# toshiba_board.net
KiCad netlist of a schematic drawn in EAGLE
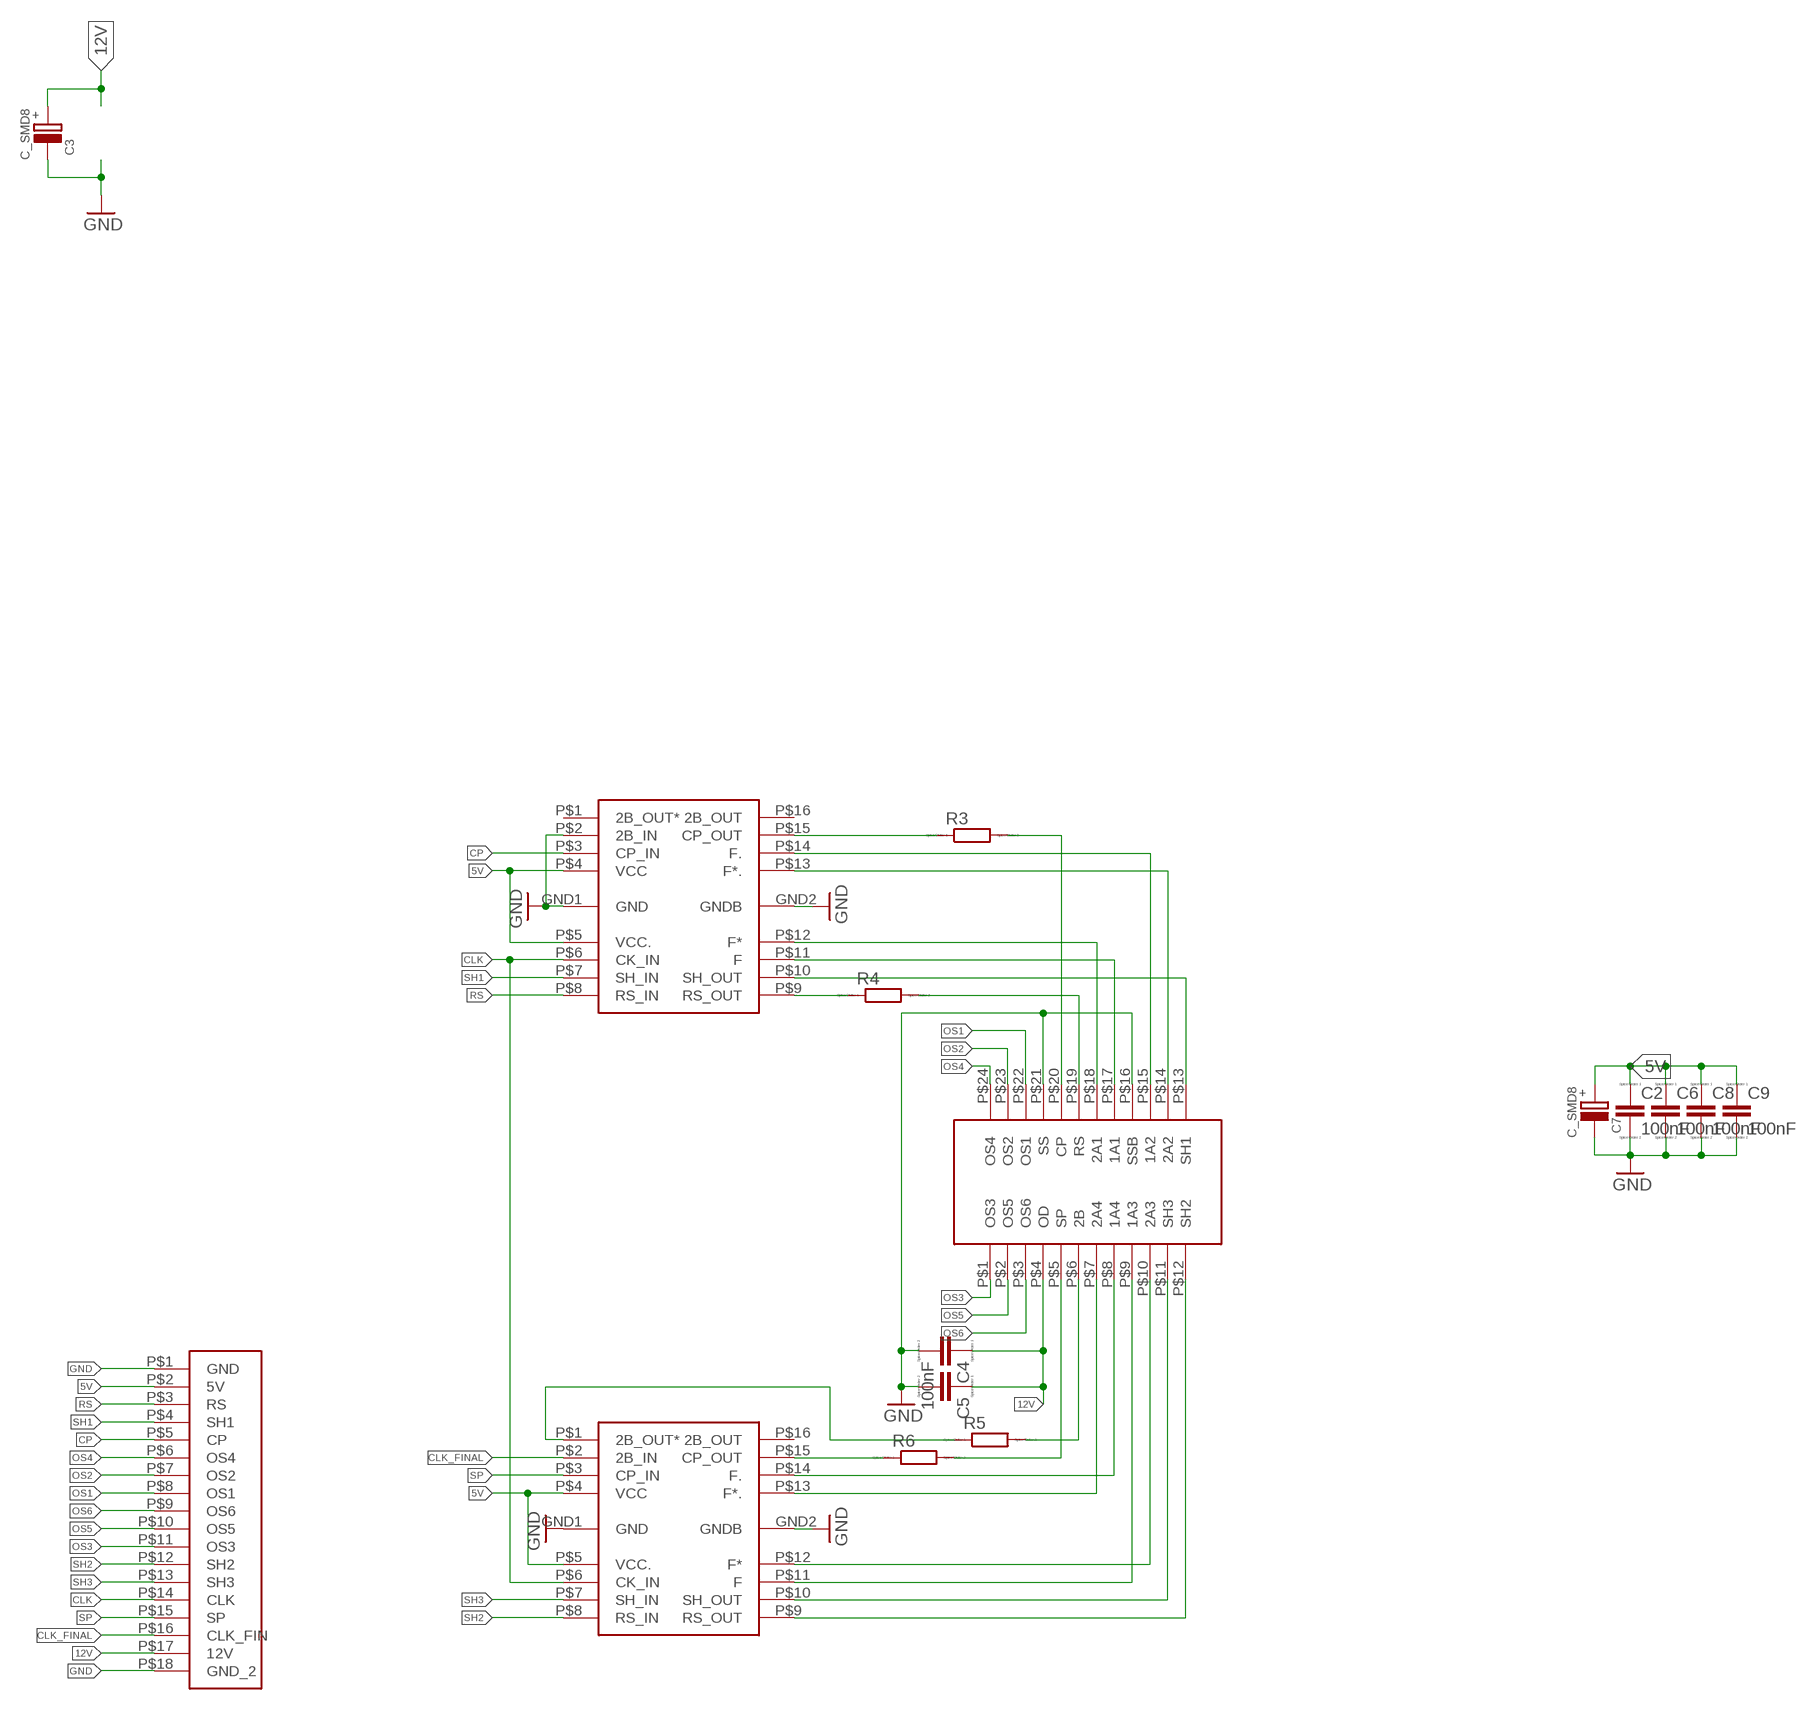
[diagram p0: schematic, sheet 1]

(export (version "E")
  (design (tool "Eeschema 10.0.6"))
  (components
    (comp (ref "C2")
      (value "100nF")
      (footprint "eagle-import:C0603")
      (libsource (lib "eagle-import") (part "C-EUC0603"))
    )
    (comp (ref "C3")
      (value "C_SMD8")
      (footprint "eagle-import:C-SMD-8MM")
      (libsource (lib "eagle-import") (part "C_SMD8"))
    )
    (comp (ref "C4")
      (value "100nF")
      (footprint "eagle-import:C0603")
      (libsource (lib "eagle-import") (part "C-EUC0603"))
    )
    (comp (ref "C5")
      (value "C-EUC0805")
      (footprint "eagle-import:C0805")
      (libsource (lib "eagle-import") (part "C-EUC0805"))
    )
    (comp (ref "C6")
      (value "100nF")
      (footprint "eagle-import:C0603")
      (libsource (lib "eagle-import") (part "C-EUC0603"))
    )
    (comp (ref "C7")
      (value "C_SMD8")
      (footprint "eagle-import:C-SMD-8MM")
      (libsource (lib "eagle-import") (part "C_SMD8"))
    )
    (comp (ref "C8")
      (value "100nF")
      (footprint "eagle-import:C0603")
      (libsource (lib "eagle-import") (part "C-EUC0603"))
    )
    (comp (ref "C9")
      (value "100nF")
      (footprint "eagle-import:C0603")
      (libsource (lib "eagle-import") (part "C-EUC0603"))
    )
    (comp (ref "R3")
      (value "R-EU_R0603")
      (footprint "eagle-import:R0603")
      (libsource (lib "eagle-import") (part "R-EU_R0603"))
    )
    (comp (ref "R4")
      (value "R-EU_R0603")
      (footprint "eagle-import:R0603")
      (libsource (lib "eagle-import") (part "R-EU_R0603"))
    )
    (comp (ref "R5")
      (value "R-EU_R0603")
      (footprint "eagle-import:R0603")
      (libsource (lib "eagle-import") (part "R-EU_R0603"))
    )
    (comp (ref "R6")
      (value "R-EU_R0603")
      (footprint "eagle-import:R0603")
      (libsource (lib "eagle-import") (part "R-EU_R0603"))
    )
    (comp (ref "U$1")
      (value "TB62801F")
      (footprint "eagle-import:TB62801F")
      (libsource (lib "eagle-import") (part "TB62801F"))
    )
    (comp (ref "U$2")
      (value "TCD2700TCD")
      (footprint "eagle-import:TCD2700")
      (libsource (lib "eagle-import") (part "TCD2700TCD"))
    )
    (comp (ref "U$3")
      (value "TB62801F")
      (footprint "eagle-import:TB62801F")
      (libsource (lib "eagle-import") (part "TB62801F"))
    )
    (comp (ref "U$4")
      (value "PIN_18")
      (footprint "eagle-import:PAD_18")
      (libsource (lib "eagle-import") (part "PIN_18"))
    )
  )
  (nets
    (net (code "1") (name "5V") (class "Default")
      (node (ref "C2") (pin "1") (pinfunction "1_1") (pintype "passive"))
      (node (ref "C6") (pin "1") (pinfunction "1_1") (pintype "passive"))
      (node (ref "C7") (pin "+") (pinfunction "+_+") (pintype "bidirectional"))
      (node (ref "C8") (pin "1") (pinfunction "1_1") (pintype "passive"))
      (node (ref "C9") (pin "1") (pinfunction "1_1") (pintype "passive"))
      (node (ref "U$1") (pin "P$4") (pinfunction "VCC_P$4") (pintype "bidirectional"))
      (node (ref "U$1") (pin "P$5") (pinfunction "VCC._P$5") (pintype "bidirectional"))
      (node (ref "U$3") (pin "P$4") (pinfunction "VCC_P$4") (pintype "bidirectional"))
      (node (ref "U$3") (pin "P$5") (pinfunction "VCC._P$5") (pintype "bidirectional"))
      (node (ref "U$4") (pin "P$2") (pinfunction "5V_P$2") (pintype "bidirectional"))
    )
    (net (code "2") (name "12V") (class "Default")
      (node (ref "C3") (pin "+") (pinfunction "+_+") (pintype "bidirectional"))
      (node (ref "C4") (pin "1") (pinfunction "1_1") (pintype "passive"))
      (node (ref "C5") (pin "1") (pinfunction "1_1") (pintype "passive"))
      (node (ref "U$2") (pin "P$4") (pinfunction "OD_P$4") (pintype "bidirectional"))
      (node (ref "U$4") (pin "P$17") (pinfunction "12V_P$17") (pintype "bidirectional"))
    )
    (net (code "3") (name "CLK") (class "Default")
      (node (ref "U$1") (pin "P$6") (pinfunction "CK_IN_P$6") (pintype "bidirectional"))
      (node (ref "U$3") (pin "P$6") (pinfunction "CK_IN_P$6") (pintype "bidirectional"))
      (node (ref "U$4") (pin "P$14") (pinfunction "CLK_P$14") (pintype "bidirectional"))
    )
    (net (code "4") (name "CLK_FINAL") (class "Default")
      (node (ref "U$1") (pin "P$2") (pinfunction "2B_IN_P$2") (pintype "bidirectional"))
      (node (ref "U$4") (pin "P$16") (pinfunction "CLK_FIN_P$16") (pintype "bidirectional"))
    )
    (net (code "5") (name "CP") (class "Default")
      (node (ref "U$3") (pin "P$3") (pinfunction "CP_IN_P$3") (pintype "bidirectional"))
      (node (ref "U$4") (pin "P$5") (pinfunction "CP_P$5") (pintype "bidirectional"))
    )
    (net (code "6") (name "GND") (class "Default")
      (node (ref "C2") (pin "2") (pinfunction "2_2") (pintype "passive"))
      (node (ref "C3") (pin "-") (pinfunction "-_-") (pintype "bidirectional"))
      (node (ref "C4") (pin "2") (pinfunction "2_2") (pintype "passive"))
      (node (ref "C5") (pin "2") (pinfunction "2_2") (pintype "passive"))
      (node (ref "C6") (pin "2") (pinfunction "2_2") (pintype "passive"))
      (node (ref "C7") (pin "-") (pinfunction "-_-") (pintype "bidirectional"))
      (node (ref "C8") (pin "2") (pinfunction "2_2") (pintype "passive"))
      (node (ref "C9") (pin "2") (pinfunction "2_2") (pintype "passive"))
      (node (ref "U$1") (pin "GND1") (pinfunction "GND_GND1") (pintype "bidirectional"))
      (node (ref "U$1") (pin "GND2") (pinfunction "GNDB_GND2") (pintype "bidirectional"))
      (node (ref "U$2") (pin "P$16") (pinfunction "SSB_P$16") (pintype "bidirectional"))
      (node (ref "U$2") (pin "P$21") (pinfunction "SS_P$21") (pintype "bidirectional"))
      (node (ref "U$3") (pin "GND1") (pinfunction "GND_GND1") (pintype "bidirectional"))
      (node (ref "U$3") (pin "GND2") (pinfunction "GNDB_GND2") (pintype "bidirectional"))
      (node (ref "U$3") (pin "P$2") (pinfunction "2B_IN_P$2") (pintype "bidirectional"))
      (node (ref "U$4") (pin "P$1") (pinfunction "GND_P$1") (pintype "bidirectional"))
      (node (ref "U$4") (pin "P$18") (pinfunction "GND_2_P$18") (pintype "bidirectional"))
    )
    (net (code "7") (name "Net-(U$1-2B_OUT*)") (class "Default")
      (node (ref "R5") (pin "1") (pinfunction "1_1") (pintype "passive"))
      (node (ref "U$1") (pin "P$1") (pinfunction "2B_OUT*_P$1") (pintype "bidirectional"))
    )
    (net (code "8") (name "Net-(U$1-CP_OUT)") (class "Default")
      (node (ref "R6") (pin "1") (pinfunction "1_1") (pintype "passive"))
      (node (ref "U$1") (pin "P$15") (pinfunction "CP_OUT_P$15") (pintype "bidirectional"))
    )
    (net (code "9") (name "Net-(U$1-F)") (class "Default")
      (node (ref "U$1") (pin "P$11") (pinfunction "F_P$11") (pintype "bidirectional"))
      (node (ref "U$2") (pin "P$9") (pinfunction "1A3_P$9") (pintype "bidirectional"))
    )
    (net (code "10") (name "Net-(U$1-F*)") (class "Default")
      (node (ref "U$1") (pin "P$12") (pinfunction "F*_P$12") (pintype "bidirectional"))
      (node (ref "U$2") (pin "P$10") (pinfunction "2A3_P$10") (pintype "bidirectional"))
    )
    (net (code "11") (name "Net-(U$1-F*.)") (class "Default")
      (node (ref "U$1") (pin "P$13") (pinfunction "F*._P$13") (pintype "bidirectional"))
      (node (ref "U$2") (pin "P$7") (pinfunction "2A4_P$7") (pintype "bidirectional"))
    )
    (net (code "12") (name "Net-(U$1-F.)") (class "Default")
      (node (ref "U$1") (pin "P$14") (pinfunction "F._P$14") (pintype "bidirectional"))
      (node (ref "U$2") (pin "P$8") (pinfunction "1A4_P$8") (pintype "bidirectional"))
    )
    (net (code "13") (name "Net-(U$1-RS_OUT)") (class "Default")
      (node (ref "U$1") (pin "P$9") (pinfunction "RS_OUT_P$9") (pintype "bidirectional"))
      (node (ref "U$2") (pin "P$12") (pinfunction "SH2_P$12") (pintype "bidirectional"))
    )
    (net (code "14") (name "Net-(U$1-SH_OUT)") (class "Default")
      (node (ref "U$1") (pin "P$10") (pinfunction "SH_OUT_P$10") (pintype "bidirectional"))
      (node (ref "U$2") (pin "P$11") (pinfunction "SH3_P$11") (pintype "bidirectional"))
    )
    (net (code "15") (name "Net-(U$2-1A1)") (class "Default")
      (node (ref "U$2") (pin "P$17") (pinfunction "1A1_P$17") (pintype "bidirectional"))
      (node (ref "U$3") (pin "P$11") (pinfunction "F_P$11") (pintype "bidirectional"))
    )
    (net (code "16") (name "Net-(U$2-1A2)") (class "Default")
      (node (ref "U$2") (pin "P$15") (pinfunction "1A2_P$15") (pintype "bidirectional"))
      (node (ref "U$3") (pin "P$14") (pinfunction "F._P$14") (pintype "bidirectional"))
    )
    (net (code "17") (name "Net-(U$2-2A1)") (class "Default")
      (node (ref "U$2") (pin "P$18") (pinfunction "2A1_P$18") (pintype "bidirectional"))
      (node (ref "U$3") (pin "P$12") (pinfunction "F*_P$12") (pintype "bidirectional"))
    )
    (net (code "18") (name "Net-(U$2-2A2)") (class "Default")
      (node (ref "U$2") (pin "P$14") (pinfunction "2A2_P$14") (pintype "bidirectional"))
      (node (ref "U$3") (pin "P$13") (pinfunction "F*._P$13") (pintype "bidirectional"))
    )
    (net (code "19") (name "Net-(U$2-2B)") (class "Default")
      (node (ref "R5") (pin "2") (pinfunction "2_2") (pintype "passive"))
      (node (ref "U$2") (pin "P$6") (pinfunction "2B_P$6") (pintype "bidirectional"))
    )
    (net (code "20") (name "Net-(U$2-CP)") (class "Default")
      (node (ref "R3") (pin "2") (pinfunction "2_2") (pintype "passive"))
      (node (ref "U$2") (pin "P$20") (pinfunction "CP_P$20") (pintype "bidirectional"))
    )
    (net (code "21") (name "Net-(U$2-RS)") (class "Default")
      (node (ref "R4") (pin "2") (pinfunction "2_2") (pintype "passive"))
      (node (ref "U$2") (pin "P$19") (pinfunction "RS_P$19") (pintype "bidirectional"))
    )
    (net (code "22") (name "Net-(U$2-SH1)") (class "Default")
      (node (ref "U$2") (pin "P$13") (pinfunction "SH1_P$13") (pintype "bidirectional"))
      (node (ref "U$3") (pin "P$10") (pinfunction "SH_OUT_P$10") (pintype "bidirectional"))
    )
    (net (code "23") (name "Net-(U$2-SP)") (class "Default")
      (node (ref "R6") (pin "2") (pinfunction "2_2") (pintype "passive"))
      (node (ref "U$2") (pin "P$5") (pinfunction "SP_P$5") (pintype "bidirectional"))
    )
    (net (code "24") (name "Net-(U$3-CP_OUT)") (class "Default")
      (node (ref "R3") (pin "1") (pinfunction "1_1") (pintype "passive"))
      (node (ref "U$3") (pin "P$15") (pinfunction "CP_OUT_P$15") (pintype "bidirectional"))
    )
    (net (code "25") (name "Net-(U$3-RS_OUT)") (class "Default")
      (node (ref "R4") (pin "1") (pinfunction "1_1") (pintype "passive"))
      (node (ref "U$3") (pin "P$9") (pinfunction "RS_OUT_P$9") (pintype "bidirectional"))
    )
    (net (code "26") (name "OS1") (class "Default")
      (node (ref "U$2") (pin "P$22") (pinfunction "OS1_P$22") (pintype "bidirectional"))
      (node (ref "U$4") (pin "P$8") (pinfunction "OS1_P$8") (pintype "bidirectional"))
    )
    (net (code "27") (name "OS2") (class "Default")
      (node (ref "U$2") (pin "P$23") (pinfunction "OS2_P$23") (pintype "bidirectional"))
      (node (ref "U$4") (pin "P$7") (pinfunction "OS2_P$7") (pintype "bidirectional"))
    )
    (net (code "28") (name "OS3") (class "Default")
      (node (ref "U$2") (pin "P$1") (pinfunction "OS3_P$1") (pintype "bidirectional"))
      (node (ref "U$4") (pin "P$11") (pinfunction "OS3_P$11") (pintype "bidirectional"))
    )
    (net (code "29") (name "OS4") (class "Default")
      (node (ref "U$2") (pin "P$24") (pinfunction "OS4_P$24") (pintype "bidirectional"))
      (node (ref "U$4") (pin "P$6") (pinfunction "OS4_P$6") (pintype "bidirectional"))
    )
    (net (code "30") (name "OS5") (class "Default")
      (node (ref "U$2") (pin "P$2") (pinfunction "OS5_P$2") (pintype "bidirectional"))
      (node (ref "U$4") (pin "P$10") (pinfunction "OS5_P$10") (pintype "bidirectional"))
    )
    (net (code "31") (name "OS6") (class "Default")
      (node (ref "U$2") (pin "P$3") (pinfunction "OS6_P$3") (pintype "bidirectional"))
      (node (ref "U$4") (pin "P$9") (pinfunction "OS6_P$9") (pintype "bidirectional"))
    )
    (net (code "32") (name "RS") (class "Default")
      (node (ref "U$3") (pin "P$8") (pinfunction "RS_IN_P$8") (pintype "bidirectional"))
      (node (ref "U$4") (pin "P$3") (pinfunction "RS_P$3") (pintype "bidirectional"))
    )
    (net (code "33") (name "SH1") (class "Default")
      (node (ref "U$3") (pin "P$7") (pinfunction "SH_IN_P$7") (pintype "bidirectional"))
      (node (ref "U$4") (pin "P$4") (pinfunction "SH1_P$4") (pintype "bidirectional"))
    )
    (net (code "34") (name "SH2") (class "Default")
      (node (ref "U$1") (pin "P$8") (pinfunction "RS_IN_P$8") (pintype "bidirectional"))
      (node (ref "U$4") (pin "P$12") (pinfunction "SH2_P$12") (pintype "bidirectional"))
    )
    (net (code "35") (name "SH3") (class "Default")
      (node (ref "U$1") (pin "P$7") (pinfunction "SH_IN_P$7") (pintype "bidirectional"))
      (node (ref "U$4") (pin "P$13") (pinfunction "SH3_P$13") (pintype "bidirectional"))
    )
    (net (code "36") (name "SP") (class "Default")
      (node (ref "U$1") (pin "P$3") (pinfunction "CP_IN_P$3") (pintype "bidirectional"))
      (node (ref "U$4") (pin "P$15") (pinfunction "SP_P$15") (pintype "bidirectional"))
    )
    (net (code "37") (name "unconnected-(U$1-2B_OUT-PadP$16)") (class "Default")
      (node (ref "U$1") (pin "P$16") (pinfunction "2B_OUT_P$16") (pintype "bidirectional"))
    )
    (net (code "38") (name "unconnected-(U$3-2B_OUT*-PadP$1)") (class "Default")
      (node (ref "U$3") (pin "P$1") (pinfunction "2B_OUT*_P$1") (pintype "bidirectional"))
    )
    (net (code "39") (name "unconnected-(U$3-2B_OUT-PadP$16)") (class "Default")
      (node (ref "U$3") (pin "P$16") (pinfunction "2B_OUT_P$16") (pintype "bidirectional"))
    )
  )
)
